# M850A.net
KiCad netlist of a schematic drawn in EAGLE
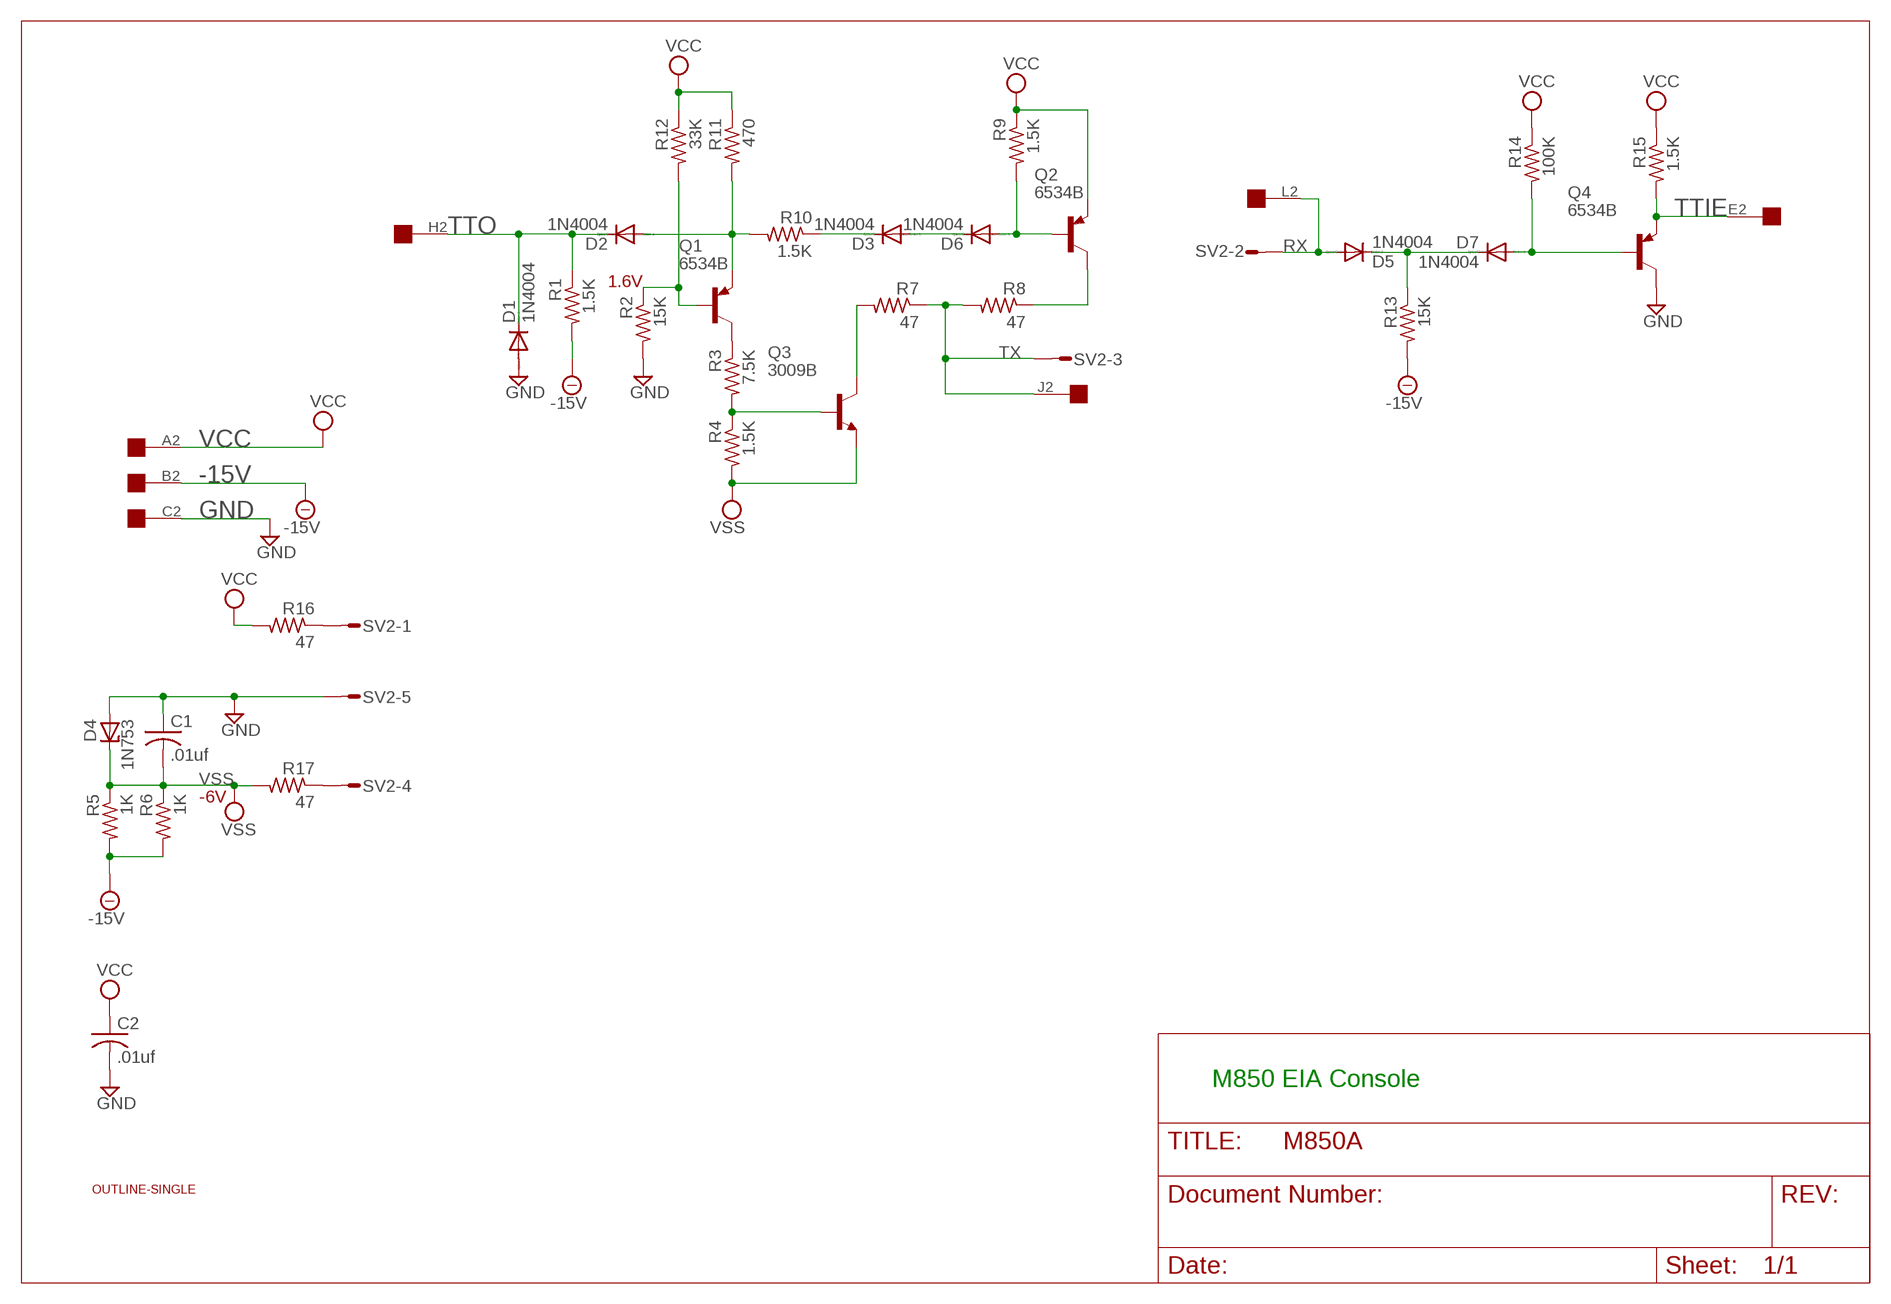
[diagram p0: schematic, sheet 1]

(export (version "E")
  (design (tool "Eeschema 10.0.6"))
  (components
    (comp (ref "C1")
      (value ".01uf")
      (footprint "eagle-import:C050-025X075")
      (libsource (lib "eagle-import") (part "C-US050-025X075"))
    )
    (comp (ref "C2")
      (value ".01uf")
      (footprint "eagle-import:C050-025X075")
      (libsource (lib "eagle-import") (part "C-US050-025X075"))
    )
    (comp (ref "D1")
      (value "1N4004")
      (footprint "eagle-import:DO35-10")
      (libsource (lib "eagle-import") (part "1N4148DO35-10"))
    )
    (comp (ref "D2")
      (value "1N4004")
      (footprint "eagle-import:DO35-10")
      (libsource (lib "eagle-import") (part "1N4148DO35-10"))
    )
    (comp (ref "D3")
      (value "1N4004")
      (footprint "eagle-import:DO35-10")
      (libsource (lib "eagle-import") (part "1N4148DO35-10"))
    )
    (comp (ref "D4")
      (value "1N753")
      (footprint "eagle-import:DO35Z10")
      (libsource (lib "eagle-import") (part "ZENER-DIODEDO35Z10"))
    )
    (comp (ref "D5")
      (value "1N4004")
      (footprint "eagle-import:DO35-10")
      (libsource (lib "eagle-import") (part "1N4148DO35-10"))
    )
    (comp (ref "D6")
      (value "1N4004")
      (footprint "eagle-import:DO35-10")
      (libsource (lib "eagle-import") (part "1N4148DO35-10"))
    )
    (comp (ref "D7")
      (value "1N4004")
      (footprint "eagle-import:DO35-10")
      (libsource (lib "eagle-import") (part "1N4148DO35-10"))
    )
    (comp (ref "EDGE")
      (value "EDGE-1")
      (footprint "eagle-import:EDGE-CON1")
      (libsource (lib "eagle-import") (part "EDGE-1"))
    )
    (comp (ref "Q1")
      (value "6534B")
      (footprint "eagle-import:TO92_")
      (libsource (lib "eagle-import") (part "-PNP-TO92/"))
    )
    (comp (ref "Q2")
      (value "6534B")
      (footprint "eagle-import:TO92_")
      (libsource (lib "eagle-import") (part "-PNP-TO92/"))
    )
    (comp (ref "Q3")
      (value "3009B")
      (footprint "eagle-import:TO18-")
      (libsource (lib "eagle-import") (part "-NPN-TO18-"))
    )
    (comp (ref "Q4")
      (value "6534B")
      (footprint "eagle-import:TO92_")
      (libsource (lib "eagle-import") (part "-PNP-TO92/"))
    )
    (comp (ref "R1")
      (value "1.5K")
      (footprint "eagle-import:0207_10")
      (libsource (lib "eagle-import") (part "R-US_0207/10"))
    )
    (comp (ref "R2")
      (value "15K")
      (footprint "eagle-import:0207_10")
      (libsource (lib "eagle-import") (part "R-US_0207/10"))
    )
    (comp (ref "R3")
      (value "7.5K")
      (footprint "eagle-import:0207_10")
      (libsource (lib "eagle-import") (part "R-US_0207/10"))
    )
    (comp (ref "R4")
      (value "1.5K")
      (footprint "eagle-import:0207_10")
      (libsource (lib "eagle-import") (part "R-US_0207/10"))
    )
    (comp (ref "R5")
      (value "1K")
      (footprint "eagle-import:0207_10")
      (libsource (lib "eagle-import") (part "R-US_0207/10"))
    )
    (comp (ref "R6")
      (value "1K")
      (footprint "eagle-import:0207_10")
      (libsource (lib "eagle-import") (part "R-US_0207/10"))
    )
    (comp (ref "R7")
      (value "47")
      (footprint "eagle-import:0207_10")
      (libsource (lib "eagle-import") (part "R-US_0207/10"))
    )
    (comp (ref "R8")
      (value "47")
      (footprint "eagle-import:0207_10")
      (libsource (lib "eagle-import") (part "R-US_0207/10"))
    )
    (comp (ref "R9")
      (value "1.5K")
      (footprint "eagle-import:0207_10")
      (libsource (lib "eagle-import") (part "R-US_0207/10"))
    )
    (comp (ref "R10")
      (value "1.5K")
      (footprint "eagle-import:0207_10")
      (libsource (lib "eagle-import") (part "R-US_0207/10"))
    )
    (comp (ref "R11")
      (value "470")
      (footprint "eagle-import:0207_10")
      (libsource (lib "eagle-import") (part "R-US_0207/10"))
    )
    (comp (ref "R12")
      (value "33K")
      (footprint "eagle-import:0207_10")
      (libsource (lib "eagle-import") (part "R-US_0207/10"))
    )
    (comp (ref "R13")
      (value "15K")
      (footprint "eagle-import:0207_10")
      (libsource (lib "eagle-import") (part "R-US_0207/10"))
    )
    (comp (ref "R14")
      (value "100K")
      (footprint "eagle-import:0207_10")
      (libsource (lib "eagle-import") (part "R-US_0207/10"))
    )
    (comp (ref "R15")
      (value "1.5K")
      (footprint "eagle-import:0207_10")
      (libsource (lib "eagle-import") (part "R-US_0207/10"))
    )
    (comp (ref "R16")
      (value "47")
      (footprint "eagle-import:0207_10")
      (libsource (lib "eagle-import") (part "R-US_0207/10"))
    )
    (comp (ref "R17")
      (value "47")
      (footprint "eagle-import:0207_10")
      (libsource (lib "eagle-import") (part "R-US_0207/10"))
    )
    (comp (ref "SV2")
      (value "L08P")
      (footprint "eagle-import:L08P")
      (libsource (lib "eagle-import") (part "L08P"))
    )
    (comp (ref "U$1")
      (value "OUTLINE-SINGLE")
      (footprint "eagle-import:SINGLE")
      (libsource (lib "eagle-import") (part "OUTLINE-SINGLE"))
    )
  )
  (nets
    (net (code "1") (name "-15V") (class "Default")
      (node (ref "EDGE") (pin "B2") (pinfunction "1_B2") (pintype "bidirectional"))
      (node (ref "R1") (pin "2") (pinfunction "2_2") (pintype "passive"))
      (node (ref "R13") (pin "2") (pinfunction "2_2") (pintype "passive"))
      (node (ref "R5") (pin "2") (pinfunction "2_2") (pintype "passive"))
      (node (ref "R6") (pin "2") (pinfunction "2_2") (pintype "passive"))
    )
    (net (code "2") (name "/RX") (class "Default")
      (node (ref "D5") (pin "A") (pinfunction "A_A") (pintype "passive"))
      (node (ref "EDGE") (pin "L2") (pinfunction "1_L2") (pintype "bidirectional"))
      (node (ref "SV2") (pin "2") (pinfunction "S_2") (pintype "passive"))
    )
    (net (code "3") (name "/TTIE") (class "Default")
      (node (ref "EDGE") (pin "E2") (pinfunction "1_E2") (pintype "bidirectional"))
      (node (ref "Q4") (pin "1") (pinfunction "E_1") (pintype "passive"))
      (node (ref "R15") (pin "2") (pinfunction "2_2") (pintype "passive"))
    )
    (net (code "4") (name "/TTO") (class "Default")
      (node (ref "D1") (pin "C") (pinfunction "C_C") (pintype "passive"))
      (node (ref "D2") (pin "C") (pinfunction "C_C") (pintype "passive"))
      (node (ref "EDGE") (pin "H2") (pinfunction "1_H2") (pintype "bidirectional"))
      (node (ref "R1") (pin "1") (pinfunction "1_1") (pintype "passive"))
    )
    (net (code "5") (name "/TX") (class "Default")
      (node (ref "EDGE") (pin "J2") (pinfunction "1_J2") (pintype "bidirectional"))
      (node (ref "R7") (pin "1") (pinfunction "1_1") (pintype "passive"))
      (node (ref "R8") (pin "2") (pinfunction "2_2") (pintype "passive"))
      (node (ref "SV2") (pin "3") (pinfunction "S_3") (pintype "passive"))
    )
    (net (code "6") (name "GND") (class "Default")
      (node (ref "C1") (pin "1") (pinfunction "1_1") (pintype "passive"))
      (node (ref "C2") (pin "2") (pinfunction "2_2") (pintype "passive"))
      (node (ref "D1") (pin "A") (pinfunction "A_A") (pintype "passive"))
      (node (ref "D4") (pin "A") (pinfunction "A_A") (pintype "passive"))
      (node (ref "EDGE") (pin "C2") (pinfunction "1_C2") (pintype "bidirectional"))
      (node (ref "Q4") (pin "3") (pinfunction "C_3") (pintype "passive"))
      (node (ref "R2") (pin "2") (pinfunction "2_2") (pintype "passive"))
      (node (ref "SV2") (pin "5") (pinfunction "S_5") (pintype "passive"))
    )
    (net (code "7") (name "Net-(D3-PadA)") (class "Default")
      (node (ref "D3") (pin "A") (pinfunction "A_A") (pintype "passive"))
      (node (ref "D6") (pin "C") (pinfunction "C_C") (pintype "passive"))
    )
    (net (code "8") (name "Net-(D3-PadC)") (class "Default")
      (node (ref "D3") (pin "C") (pinfunction "C_C") (pintype "passive"))
      (node (ref "R10") (pin "1") (pinfunction "1_1") (pintype "passive"))
    )
    (net (code "9") (name "Net-(D5-PadC)") (class "Default")
      (node (ref "D5") (pin "C") (pinfunction "C_C") (pintype "passive"))
      (node (ref "D7") (pin "C") (pinfunction "C_C") (pintype "passive"))
      (node (ref "R13") (pin "1") (pinfunction "1_1") (pintype "passive"))
    )
    (net (code "10") (name "Net-(Q1-B)") (class "Default")
      (node (ref "Q1") (pin "2") (pinfunction "B_2") (pintype "passive"))
      (node (ref "R12") (pin "2") (pinfunction "2_2") (pintype "passive"))
      (node (ref "R2") (pin "1") (pinfunction "1_1") (pintype "passive"))
    )
    (net (code "11") (name "Net-(Q1-C)") (class "Default")
      (node (ref "Q1") (pin "3") (pinfunction "C_3") (pintype "passive"))
      (node (ref "R3") (pin "1") (pinfunction "1_1") (pintype "passive"))
    )
    (net (code "12") (name "Net-(Q1-E)") (class "Default")
      (node (ref "D2") (pin "A") (pinfunction "A_A") (pintype "passive"))
      (node (ref "Q1") (pin "1") (pinfunction "E_1") (pintype "passive"))
      (node (ref "R10") (pin "2") (pinfunction "2_2") (pintype "passive"))
      (node (ref "R11") (pin "2") (pinfunction "2_2") (pintype "passive"))
    )
    (net (code "13") (name "Net-(Q2-B)") (class "Default")
      (node (ref "D6") (pin "A") (pinfunction "A_A") (pintype "passive"))
      (node (ref "Q2") (pin "2") (pinfunction "B_2") (pintype "passive"))
      (node (ref "R9") (pin "2") (pinfunction "2_2") (pintype "passive"))
    )
    (net (code "14") (name "Net-(Q2-C)") (class "Default")
      (node (ref "Q2") (pin "3") (pinfunction "C_3") (pintype "passive"))
      (node (ref "R8") (pin "1") (pinfunction "1_1") (pintype "passive"))
    )
    (net (code "15") (name "Net-(Q3-B)") (class "Default")
      (node (ref "Q3") (pin "2") (pinfunction "B_2") (pintype "passive"))
      (node (ref "R3") (pin "2") (pinfunction "2_2") (pintype "passive"))
      (node (ref "R4") (pin "1") (pinfunction "1_1") (pintype "passive"))
    )
    (net (code "16") (name "Net-(Q3-C)") (class "Default")
      (node (ref "Q3") (pin "3") (pinfunction "C_3") (pintype "passive"))
      (node (ref "R7") (pin "2") (pinfunction "2_2") (pintype "passive"))
    )
    (net (code "17") (name "Net-(Q4-B)") (class "Default")
      (node (ref "D7") (pin "A") (pinfunction "A_A") (pintype "passive"))
      (node (ref "Q4") (pin "2") (pinfunction "B_2") (pintype "passive"))
      (node (ref "R14") (pin "2") (pinfunction "2_2") (pintype "passive"))
    )
    (net (code "18") (name "Net-(SV2A-S)") (class "Default")
      (node (ref "R16") (pin "1") (pinfunction "1_1") (pintype "passive"))
      (node (ref "SV2") (pin "1") (pinfunction "S_1") (pintype "passive"))
    )
    (net (code "19") (name "Net-(SV2D-S)") (class "Default")
      (node (ref "R17") (pin "1") (pinfunction "1_1") (pintype "passive"))
      (node (ref "SV2") (pin "4") (pinfunction "S_4") (pintype "passive"))
    )
    (net (code "20") (name "VCC") (class "Default")
      (node (ref "C2") (pin "1") (pinfunction "1_1") (pintype "passive"))
      (node (ref "EDGE") (pin "A2") (pinfunction "1_A2") (pintype "bidirectional"))
      (node (ref "Q2") (pin "1") (pinfunction "E_1") (pintype "passive"))
      (node (ref "R11") (pin "1") (pinfunction "1_1") (pintype "passive"))
      (node (ref "R12") (pin "1") (pinfunction "1_1") (pintype "passive"))
      (node (ref "R14") (pin "1") (pinfunction "1_1") (pintype "passive"))
      (node (ref "R15") (pin "1") (pinfunction "1_1") (pintype "passive"))
      (node (ref "R16") (pin "2") (pinfunction "2_2") (pintype "passive"))
      (node (ref "R9") (pin "1") (pinfunction "1_1") (pintype "passive"))
    )
    (net (code "21") (name "VSS") (class "Default")
      (node (ref "C1") (pin "2") (pinfunction "2_2") (pintype "passive"))
      (node (ref "D4") (pin "C") (pinfunction "C_C") (pintype "passive"))
      (node (ref "Q3") (pin "1") (pinfunction "E_1") (pintype "passive"))
      (node (ref "R17") (pin "2") (pinfunction "2_2") (pintype "passive"))
      (node (ref "R4") (pin "2") (pinfunction "2_2") (pintype "passive"))
      (node (ref "R5") (pin "1") (pinfunction "1_1") (pintype "passive"))
      (node (ref "R6") (pin "1") (pinfunction "1_1") (pintype "passive"))
    )
  )
)
